# FPGA_UNUSED.net
KiCad netlist of a schematic drawn in Altium Designer
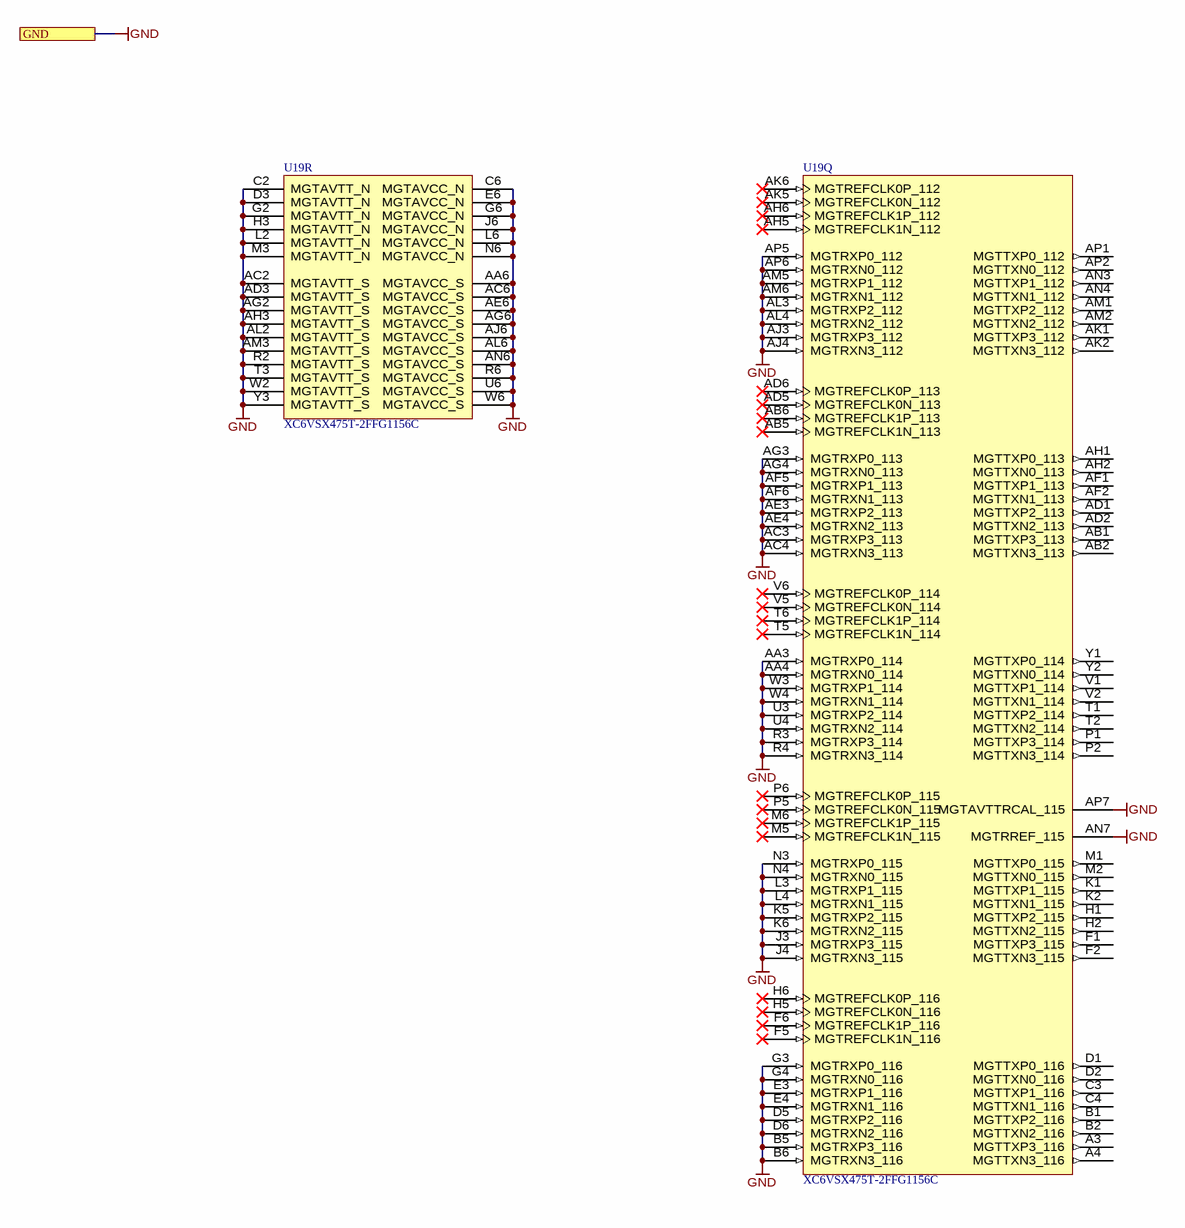
[diagram p0: FPGA_UNUSED.SchDoc]

(export (version "E")
  (design (tool "Eeschema 10.0.6"))
  (components
    (comp (ref "U19")
      (value "XC6VSX475T-2FFG1156C")
      (footprint "FFG1156")
      (libsource (lib "Altium Content Vault") (part "FPGA-XVR6-XC6VXXXXXT-GA1156"))
    )
  )
  (nets
    (net (code "1") (name "GND") (class "Default")
      (node (ref "U19") (pin "AA3") (pinfunction "MGTRXP0_114_AA3") (pintype "input"))
      (node (ref "U19") (pin "AA4") (pinfunction "MGTRXN0_114_AA4") (pintype "input"))
      (node (ref "U19") (pin "AA6") (pinfunction "MGTAVCC_S_AA6") (pintype "power_in"))
      (node (ref "U19") (pin "AC2") (pinfunction "MGTAVTT_S_AC2") (pintype "power_in"))
      (node (ref "U19") (pin "AC3") (pinfunction "MGTRXP3_113_AC3") (pintype "input"))
      (node (ref "U19") (pin "AC4") (pinfunction "MGTRXN3_113_AC4") (pintype "input"))
      (node (ref "U19") (pin "AC6") (pinfunction "MGTAVCC_S_AC6") (pintype "power_in"))
      (node (ref "U19") (pin "AD3") (pinfunction "MGTAVTT_S_AD3") (pintype "power_in"))
      (node (ref "U19") (pin "AE3") (pinfunction "MGTRXP2_113_AE3") (pintype "input"))
      (node (ref "U19") (pin "AE4") (pinfunction "MGTRXN2_113_AE4") (pintype "input"))
      (node (ref "U19") (pin "AE6") (pinfunction "MGTAVCC_S_AE6") (pintype "power_in"))
      (node (ref "U19") (pin "AF5") (pinfunction "MGTRXP1_113_AF5") (pintype "input"))
      (node (ref "U19") (pin "AF6") (pinfunction "MGTRXN1_113_AF6") (pintype "input"))
      (node (ref "U19") (pin "AG2") (pinfunction "MGTAVTT_S_AG2") (pintype "power_in"))
      (node (ref "U19") (pin "AG3") (pinfunction "MGTRXP0_113_AG3") (pintype "input"))
      (node (ref "U19") (pin "AG4") (pinfunction "MGTRXN0_113_AG4") (pintype "input"))
      (node (ref "U19") (pin "AG6") (pinfunction "MGTAVCC_S_AG6") (pintype "power_in"))
      (node (ref "U19") (pin "AH3") (pinfunction "MGTAVTT_S_AH3") (pintype "power_in"))
      (node (ref "U19") (pin "AJ3") (pinfunction "MGTRXP3_112_AJ3") (pintype "input"))
      (node (ref "U19") (pin "AJ4") (pinfunction "MGTRXN3_112_AJ4") (pintype "input"))
      (node (ref "U19") (pin "AJ6") (pinfunction "MGTAVCC_S_AJ6") (pintype "power_in"))
      (node (ref "U19") (pin "AL2") (pinfunction "MGTAVTT_S_AL2") (pintype "power_in"))
      (node (ref "U19") (pin "AL3") (pinfunction "MGTRXP2_112_AL3") (pintype "input"))
      (node (ref "U19") (pin "AL4") (pinfunction "MGTRXN2_112_AL4") (pintype "input"))
      (node (ref "U19") (pin "AL6") (pinfunction "MGTAVCC_S_AL6") (pintype "power_in"))
      (node (ref "U19") (pin "AM3") (pinfunction "MGTAVTT_S_AM3") (pintype "power_in"))
      (node (ref "U19") (pin "AM5") (pinfunction "MGTRXP1_112_AM5") (pintype "input"))
      (node (ref "U19") (pin "AM6") (pinfunction "MGTRXN1_112_AM6") (pintype "input"))
      (node (ref "U19") (pin "AN6") (pinfunction "MGTAVCC_S_AN6") (pintype "power_in"))
      (node (ref "U19") (pin "AN7") (pinfunction "MGTRREF_115_AN7") (pintype "passive"))
      (node (ref "U19") (pin "AP5") (pinfunction "MGTRXP0_112_AP5") (pintype "input"))
      (node (ref "U19") (pin "AP6") (pinfunction "MGTRXN0_112_AP6") (pintype "input"))
      (node (ref "U19") (pin "AP7") (pinfunction "MGTAVTTRCAL_115_AP7") (pintype "passive"))
      (node (ref "U19") (pin "B5") (pinfunction "MGTRXP3_116_B5") (pintype "input"))
      (node (ref "U19") (pin "B6") (pinfunction "MGTRXN3_116_B6") (pintype "input"))
      (node (ref "U19") (pin "C2") (pinfunction "MGTAVTT_N_C2") (pintype "power_in"))
      (node (ref "U19") (pin "C6") (pinfunction "MGTAVCC_N_C6") (pintype "power_in"))
      (node (ref "U19") (pin "D3") (pinfunction "MGTAVTT_N_D3") (pintype "power_in"))
      (node (ref "U19") (pin "D5") (pinfunction "MGTRXP2_116_D5") (pintype "input"))
      (node (ref "U19") (pin "D6") (pinfunction "MGTRXN2_116_D6") (pintype "input"))
      (node (ref "U19") (pin "E3") (pinfunction "MGTRXP1_116_E3") (pintype "input"))
      (node (ref "U19") (pin "E4") (pinfunction "MGTRXN1_116_E4") (pintype "input"))
      (node (ref "U19") (pin "E6") (pinfunction "MGTAVCC_N_E6") (pintype "power_in"))
      (node (ref "U19") (pin "G2") (pinfunction "MGTAVTT_N_G2") (pintype "power_in"))
      (node (ref "U19") (pin "G3") (pinfunction "MGTRXP0_116_G3") (pintype "input"))
      (node (ref "U19") (pin "G4") (pinfunction "MGTRXN0_116_G4") (pintype "input"))
      (node (ref "U19") (pin "G6") (pinfunction "MGTAVCC_N_G6") (pintype "power_in"))
      (node (ref "U19") (pin "H3") (pinfunction "MGTAVTT_N_H3") (pintype "power_in"))
      (node (ref "U19") (pin "J3") (pinfunction "MGTRXP3_115_J3") (pintype "input"))
      (node (ref "U19") (pin "J4") (pinfunction "MGTRXN3_115_J4") (pintype "input"))
      (node (ref "U19") (pin "J6") (pinfunction "MGTAVCC_N_J6") (pintype "power_in"))
      (node (ref "U19") (pin "K5") (pinfunction "MGTRXP2_115_K5") (pintype "input"))
      (node (ref "U19") (pin "K6") (pinfunction "MGTRXN2_115_K6") (pintype "input"))
      (node (ref "U19") (pin "L2") (pinfunction "MGTAVTT_N_L2") (pintype "power_in"))
      (node (ref "U19") (pin "L3") (pinfunction "MGTRXP1_115_L3") (pintype "input"))
      (node (ref "U19") (pin "L4") (pinfunction "MGTRXN1_115_L4") (pintype "input"))
      (node (ref "U19") (pin "L6") (pinfunction "MGTAVCC_N_L6") (pintype "power_in"))
      (node (ref "U19") (pin "M3") (pinfunction "MGTAVTT_N_M3") (pintype "power_in"))
      (node (ref "U19") (pin "N3") (pinfunction "MGTRXP0_115_N3") (pintype "input"))
      (node (ref "U19") (pin "N4") (pinfunction "MGTRXN0_115_N4") (pintype "input"))
      (node (ref "U19") (pin "N6") (pinfunction "MGTAVCC_N_N6") (pintype "power_in"))
      (node (ref "U19") (pin "R2") (pinfunction "MGTAVTT_S_R2") (pintype "power_in"))
      (node (ref "U19") (pin "R3") (pinfunction "MGTRXP3_114_R3") (pintype "input"))
      (node (ref "U19") (pin "R4") (pinfunction "MGTRXN3_114_R4") (pintype "input"))
      (node (ref "U19") (pin "R6") (pinfunction "MGTAVCC_S_R6") (pintype "power_in"))
      (node (ref "U19") (pin "T3") (pinfunction "MGTAVTT_S_T3") (pintype "power_in"))
      (node (ref "U19") (pin "U3") (pinfunction "MGTRXP2_114_U3") (pintype "input"))
      (node (ref "U19") (pin "U4") (pinfunction "MGTRXN2_114_U4") (pintype "input"))
      (node (ref "U19") (pin "U6") (pinfunction "MGTAVCC_S_U6") (pintype "power_in"))
      (node (ref "U19") (pin "W2") (pinfunction "MGTAVTT_S_W2") (pintype "power_in"))
      (node (ref "U19") (pin "W3") (pinfunction "MGTRXP1_114_W3") (pintype "input"))
      (node (ref "U19") (pin "W4") (pinfunction "MGTRXN1_114_W4") (pintype "input"))
      (node (ref "U19") (pin "W6") (pinfunction "MGTAVCC_S_W6") (pintype "power_in"))
      (node (ref "U19") (pin "Y3") (pinfunction "MGTAVTT_S_Y3") (pintype "power_in"))
    )
    (net (code "2") (name "unconnected-(U19Q-MGTREFCLK0N_112-PadAK5)") (class "Default")
      (node (ref "U19") (pin "AK5") (pinfunction "MGTREFCLK0N_112_AK5") (pintype "input+no_connect"))
    )
    (net (code "3") (name "unconnected-(U19Q-MGTREFCLK0N_113-PadAD5)") (class "Default")
      (node (ref "U19") (pin "AD5") (pinfunction "MGTREFCLK0N_113_AD5") (pintype "input+no_connect"))
    )
    (net (code "4") (name "unconnected-(U19Q-MGTREFCLK0N_114-PadV5)") (class "Default")
      (node (ref "U19") (pin "V5") (pinfunction "MGTREFCLK0N_114_V5") (pintype "input+no_connect"))
    )
    (net (code "5") (name "unconnected-(U19Q-MGTREFCLK0N_115-PadP5)") (class "Default")
      (node (ref "U19") (pin "P5") (pinfunction "MGTREFCLK0N_115_P5") (pintype "input+no_connect"))
    )
    (net (code "6") (name "unconnected-(U19Q-MGTREFCLK0N_116-PadH5)") (class "Default")
      (node (ref "U19") (pin "H5") (pinfunction "MGTREFCLK0N_116_H5") (pintype "input+no_connect"))
    )
    (net (code "7") (name "unconnected-(U19Q-MGTREFCLK0P_112-PadAK6)") (class "Default")
      (node (ref "U19") (pin "AK6") (pinfunction "MGTREFCLK0P_112_AK6") (pintype "input+no_connect"))
    )
    (net (code "8") (name "unconnected-(U19Q-MGTREFCLK0P_113-PadAD6)") (class "Default")
      (node (ref "U19") (pin "AD6") (pinfunction "MGTREFCLK0P_113_AD6") (pintype "input+no_connect"))
    )
    (net (code "9") (name "unconnected-(U19Q-MGTREFCLK0P_114-PadV6)") (class "Default")
      (node (ref "U19") (pin "V6") (pinfunction "MGTREFCLK0P_114_V6") (pintype "input+no_connect"))
    )
    (net (code "10") (name "unconnected-(U19Q-MGTREFCLK0P_115-PadP6)") (class "Default")
      (node (ref "U19") (pin "P6") (pinfunction "MGTREFCLK0P_115_P6") (pintype "input+no_connect"))
    )
    (net (code "11") (name "unconnected-(U19Q-MGTREFCLK0P_116-PadH6)") (class "Default")
      (node (ref "U19") (pin "H6") (pinfunction "MGTREFCLK0P_116_H6") (pintype "input+no_connect"))
    )
    (net (code "12") (name "unconnected-(U19Q-MGTREFCLK1N_112-PadAH5)") (class "Default")
      (node (ref "U19") (pin "AH5") (pinfunction "MGTREFCLK1N_112_AH5") (pintype "input+no_connect"))
    )
    (net (code "13") (name "unconnected-(U19Q-MGTREFCLK1N_113-PadAB5)") (class "Default")
      (node (ref "U19") (pin "AB5") (pinfunction "MGTREFCLK1N_113_AB5") (pintype "input+no_connect"))
    )
    (net (code "14") (name "unconnected-(U19Q-MGTREFCLK1N_114-PadT5)") (class "Default")
      (node (ref "U19") (pin "T5") (pinfunction "MGTREFCLK1N_114_T5") (pintype "input+no_connect"))
    )
    (net (code "15") (name "unconnected-(U19Q-MGTREFCLK1N_115-PadM5)") (class "Default")
      (node (ref "U19") (pin "M5") (pinfunction "MGTREFCLK1N_115_M5") (pintype "input+no_connect"))
    )
    (net (code "16") (name "unconnected-(U19Q-MGTREFCLK1N_116-PadF5)") (class "Default")
      (node (ref "U19") (pin "F5") (pinfunction "MGTREFCLK1N_116_F5") (pintype "input+no_connect"))
    )
    (net (code "17") (name "unconnected-(U19Q-MGTREFCLK1P_112-PadAH6)") (class "Default")
      (node (ref "U19") (pin "AH6") (pinfunction "MGTREFCLK1P_112_AH6") (pintype "input+no_connect"))
    )
    (net (code "18") (name "unconnected-(U19Q-MGTREFCLK1P_113-PadAB6)") (class "Default")
      (node (ref "U19") (pin "AB6") (pinfunction "MGTREFCLK1P_113_AB6") (pintype "input+no_connect"))
    )
    (net (code "19") (name "unconnected-(U19Q-MGTREFCLK1P_114-PadT6)") (class "Default")
      (node (ref "U19") (pin "T6") (pinfunction "MGTREFCLK1P_114_T6") (pintype "input+no_connect"))
    )
    (net (code "20") (name "unconnected-(U19Q-MGTREFCLK1P_115-PadM6)") (class "Default")
      (node (ref "U19") (pin "M6") (pinfunction "MGTREFCLK1P_115_M6") (pintype "input+no_connect"))
    )
    (net (code "21") (name "unconnected-(U19Q-MGTREFCLK1P_116-PadF6)") (class "Default")
      (node (ref "U19") (pin "F6") (pinfunction "MGTREFCLK1P_116_F6") (pintype "input+no_connect"))
    )
    (net (code "22") (name "unconnected-(U19Q-MGTTXN0_112-PadAP2)") (class "Default")
      (node (ref "U19") (pin "AP2") (pinfunction "MGTTXN0_112_AP2") (pintype "output"))
    )
    (net (code "23") (name "unconnected-(U19Q-MGTTXN0_113-PadAH2)") (class "Default")
      (node (ref "U19") (pin "AH2") (pinfunction "MGTTXN0_113_AH2") (pintype "output"))
    )
    (net (code "24") (name "unconnected-(U19Q-MGTTXN0_114-PadY2)") (class "Default")
      (node (ref "U19") (pin "Y2") (pinfunction "MGTTXN0_114_Y2") (pintype "output"))
    )
    (net (code "25") (name "unconnected-(U19Q-MGTTXN0_115-PadM2)") (class "Default")
      (node (ref "U19") (pin "M2") (pinfunction "MGTTXN0_115_M2") (pintype "output"))
    )
    (net (code "26") (name "unconnected-(U19Q-MGTTXN0_116-PadD2)") (class "Default")
      (node (ref "U19") (pin "D2") (pinfunction "MGTTXN0_116_D2") (pintype "output"))
    )
    (net (code "27") (name "unconnected-(U19Q-MGTTXN1_112-PadAN4)") (class "Default")
      (node (ref "U19") (pin "AN4") (pinfunction "MGTTXN1_112_AN4") (pintype "output"))
    )
    (net (code "28") (name "unconnected-(U19Q-MGTTXN1_113-PadAF2)") (class "Default")
      (node (ref "U19") (pin "AF2") (pinfunction "MGTTXN1_113_AF2") (pintype "output"))
    )
    (net (code "29") (name "unconnected-(U19Q-MGTTXN1_114-PadV2)") (class "Default")
      (node (ref "U19") (pin "V2") (pinfunction "MGTTXN1_114_V2") (pintype "output"))
    )
    (net (code "30") (name "unconnected-(U19Q-MGTTXN1_115-PadK2)") (class "Default")
      (node (ref "U19") (pin "K2") (pinfunction "MGTTXN1_115_K2") (pintype "output"))
    )
    (net (code "31") (name "unconnected-(U19Q-MGTTXN1_116-PadC4)") (class "Default")
      (node (ref "U19") (pin "C4") (pinfunction "MGTTXN1_116_C4") (pintype "output"))
    )
    (net (code "32") (name "unconnected-(U19Q-MGTTXN2_112-PadAM2)") (class "Default")
      (node (ref "U19") (pin "AM2") (pinfunction "MGTTXN2_112_AM2") (pintype "output"))
    )
    (net (code "33") (name "unconnected-(U19Q-MGTTXN2_113-PadAD2)") (class "Default")
      (node (ref "U19") (pin "AD2") (pinfunction "MGTTXN2_113_AD2") (pintype "output"))
    )
    (net (code "34") (name "unconnected-(U19Q-MGTTXN2_114-PadT2)") (class "Default")
      (node (ref "U19") (pin "T2") (pinfunction "MGTTXN2_114_T2") (pintype "output"))
    )
    (net (code "35") (name "unconnected-(U19Q-MGTTXN2_115-PadH2)") (class "Default")
      (node (ref "U19") (pin "H2") (pinfunction "MGTTXN2_115_H2") (pintype "output"))
    )
    (net (code "36") (name "unconnected-(U19Q-MGTTXN2_116-PadB2)") (class "Default")
      (node (ref "U19") (pin "B2") (pinfunction "MGTTXN2_116_B2") (pintype "output"))
    )
    (net (code "37") (name "unconnected-(U19Q-MGTTXN3_112-PadAK2)") (class "Default")
      (node (ref "U19") (pin "AK2") (pinfunction "MGTTXN3_112_AK2") (pintype "output"))
    )
    (net (code "38") (name "unconnected-(U19Q-MGTTXN3_113-PadAB2)") (class "Default")
      (node (ref "U19") (pin "AB2") (pinfunction "MGTTXN3_113_AB2") (pintype "output"))
    )
    (net (code "39") (name "unconnected-(U19Q-MGTTXN3_114-PadP2)") (class "Default")
      (node (ref "U19") (pin "P2") (pinfunction "MGTTXN3_114_P2") (pintype "output"))
    )
    (net (code "40") (name "unconnected-(U19Q-MGTTXN3_115-PadF2)") (class "Default")
      (node (ref "U19") (pin "F2") (pinfunction "MGTTXN3_115_F2") (pintype "output"))
    )
    (net (code "41") (name "unconnected-(U19Q-MGTTXN3_116-PadA4)") (class "Default")
      (node (ref "U19") (pin "A4") (pinfunction "MGTTXN3_116_A4") (pintype "output"))
    )
    (net (code "42") (name "unconnected-(U19Q-MGTTXP0_112-PadAP1)") (class "Default")
      (node (ref "U19") (pin "AP1") (pinfunction "MGTTXP0_112_AP1") (pintype "output"))
    )
    (net (code "43") (name "unconnected-(U19Q-MGTTXP0_113-PadAH1)") (class "Default")
      (node (ref "U19") (pin "AH1") (pinfunction "MGTTXP0_113_AH1") (pintype "output"))
    )
    (net (code "44") (name "unconnected-(U19Q-MGTTXP0_114-PadY1)") (class "Default")
      (node (ref "U19") (pin "Y1") (pinfunction "MGTTXP0_114_Y1") (pintype "output"))
    )
    (net (code "45") (name "unconnected-(U19Q-MGTTXP0_115-PadM1)") (class "Default")
      (node (ref "U19") (pin "M1") (pinfunction "MGTTXP0_115_M1") (pintype "output"))
    )
    (net (code "46") (name "unconnected-(U19Q-MGTTXP0_116-PadD1)") (class "Default")
      (node (ref "U19") (pin "D1") (pinfunction "MGTTXP0_116_D1") (pintype "output"))
    )
    (net (code "47") (name "unconnected-(U19Q-MGTTXP1_112-PadAN3)") (class "Default")
      (node (ref "U19") (pin "AN3") (pinfunction "MGTTXP1_112_AN3") (pintype "output"))
    )
    (net (code "48") (name "unconnected-(U19Q-MGTTXP1_113-PadAF1)") (class "Default")
      (node (ref "U19") (pin "AF1") (pinfunction "MGTTXP1_113_AF1") (pintype "output"))
    )
    (net (code "49") (name "unconnected-(U19Q-MGTTXP1_114-PadV1)") (class "Default")
      (node (ref "U19") (pin "V1") (pinfunction "MGTTXP1_114_V1") (pintype "output"))
    )
    (net (code "50") (name "unconnected-(U19Q-MGTTXP1_115-PadK1)") (class "Default")
      (node (ref "U19") (pin "K1") (pinfunction "MGTTXP1_115_K1") (pintype "output"))
    )
    (net (code "51") (name "unconnected-(U19Q-MGTTXP1_116-PadC3)") (class "Default")
      (node (ref "U19") (pin "C3") (pinfunction "MGTTXP1_116_C3") (pintype "output"))
    )
    (net (code "52") (name "unconnected-(U19Q-MGTTXP2_112-PadAM1)") (class "Default")
      (node (ref "U19") (pin "AM1") (pinfunction "MGTTXP2_112_AM1") (pintype "output"))
    )
    (net (code "53") (name "unconnected-(U19Q-MGTTXP2_113-PadAD1)") (class "Default")
      (node (ref "U19") (pin "AD1") (pinfunction "MGTTXP2_113_AD1") (pintype "output"))
    )
    (net (code "54") (name "unconnected-(U19Q-MGTTXP2_114-PadT1)") (class "Default")
      (node (ref "U19") (pin "T1") (pinfunction "MGTTXP2_114_T1") (pintype "output"))
    )
    (net (code "55") (name "unconnected-(U19Q-MGTTXP2_115-PadH1)") (class "Default")
      (node (ref "U19") (pin "H1") (pinfunction "MGTTXP2_115_H1") (pintype "output"))
    )
    (net (code "56") (name "unconnected-(U19Q-MGTTXP2_116-PadB1)") (class "Default")
      (node (ref "U19") (pin "B1") (pinfunction "MGTTXP2_116_B1") (pintype "output"))
    )
    (net (code "57") (name "unconnected-(U19Q-MGTTXP3_112-PadAK1)") (class "Default")
      (node (ref "U19") (pin "AK1") (pinfunction "MGTTXP3_112_AK1") (pintype "output"))
    )
    (net (code "58") (name "unconnected-(U19Q-MGTTXP3_113-PadAB1)") (class "Default")
      (node (ref "U19") (pin "AB1") (pinfunction "MGTTXP3_113_AB1") (pintype "output"))
    )
    (net (code "59") (name "unconnected-(U19Q-MGTTXP3_114-PadP1)") (class "Default")
      (node (ref "U19") (pin "P1") (pinfunction "MGTTXP3_114_P1") (pintype "output"))
    )
    (net (code "60") (name "unconnected-(U19Q-MGTTXP3_115-PadF1)") (class "Default")
      (node (ref "U19") (pin "F1") (pinfunction "MGTTXP3_115_F1") (pintype "output"))
    )
    (net (code "61") (name "unconnected-(U19Q-MGTTXP3_116-PadA3)") (class "Default")
      (node (ref "U19") (pin "A3") (pinfunction "MGTTXP3_116_A3") (pintype "output"))
    )
  )
)
